# Volts_Sample.net
KiCad netlist of a schematic drawn in Altium Designer
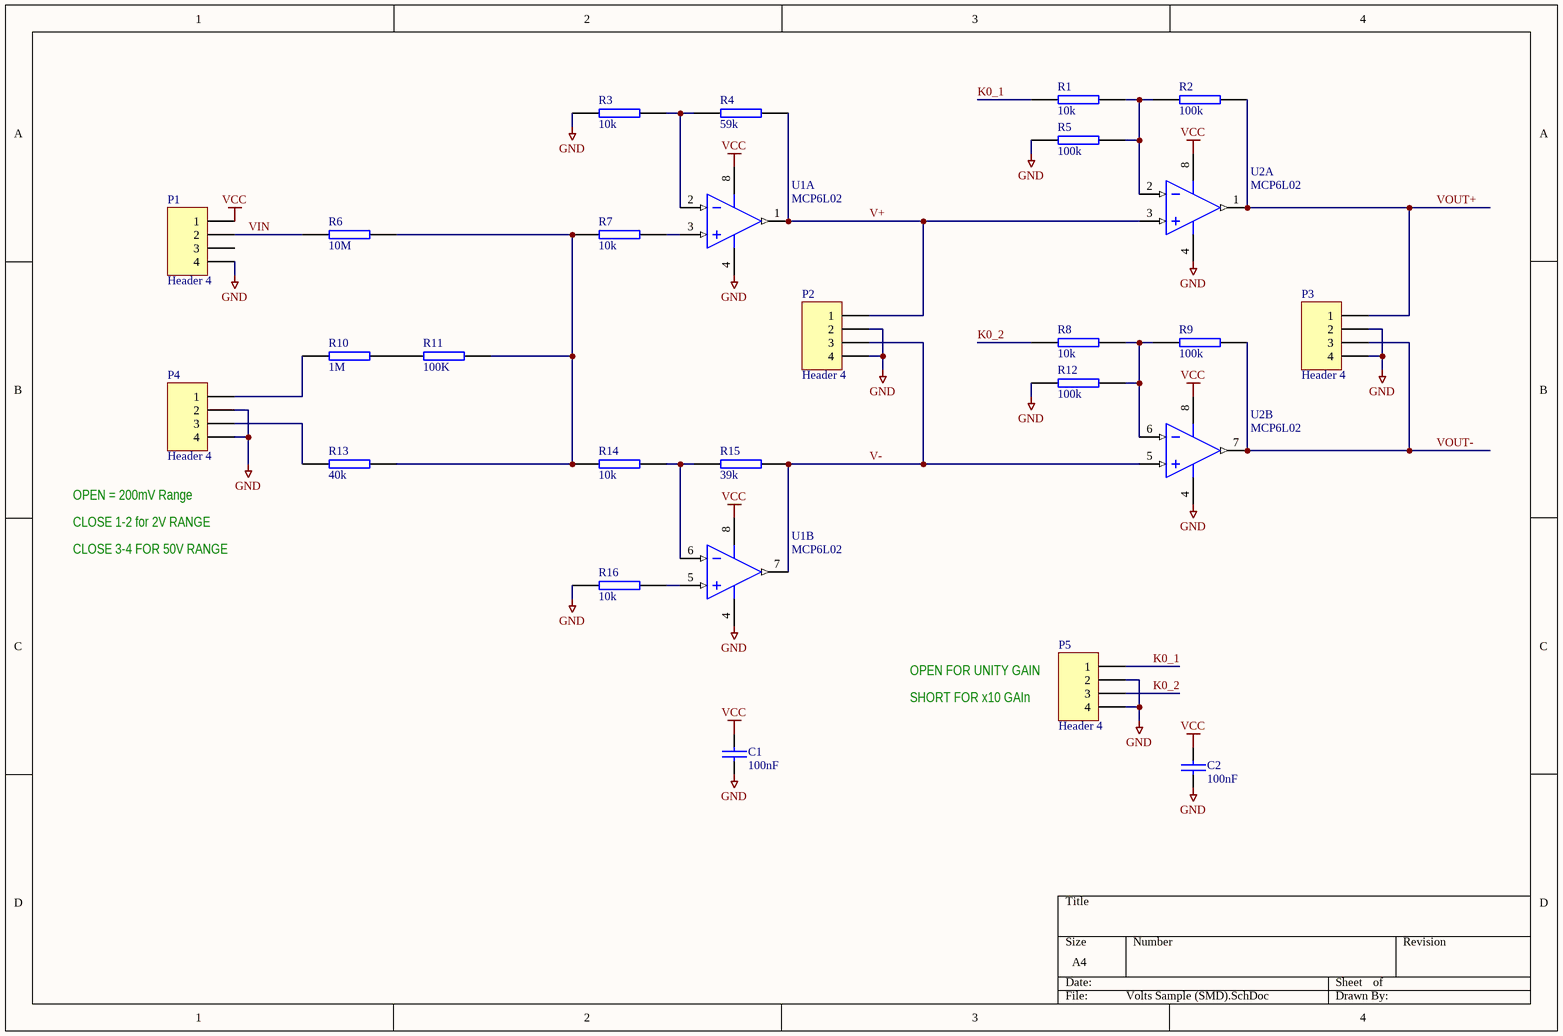
[diagram p0: Volts Sample (SMD).SchDoc]

(export (version "E")
  (design (tool "Eeschema 10.0.6"))
  (components
    (comp (ref "C1")
      (value "100nF")
      (footprint "CAP (3D) - 0603")
      (description "CAPACITOR SMD 0603")
      (fields
        (field (name "MOUSER PART NO.") "81-GRM155R61C104KA8D")
        (field (name "FARNELL PART NO.") "1414610")
      )
      (libsource (lib "Mi-Call Schematic") (part "CAP"))
    )
    (comp (ref "C2")
      (value "100nF")
      (footprint "CAP (3D) - 0603")
      (description "CAPACITOR SMD 0603")
      (fields
        (field (name "MOUSER PART NO.") "81-GRM155R61C104KA8D")
        (field (name "FARNELL PART NO.") "1414610")
      )
      (libsource (lib "Mi-Call Schematic") (part "CAP"))
    )
    (comp (ref "P1")
      (value "Header 4")
      (footprint "HDR1X4")
      (description "Header, 4-Pin")
      (fields (field (name "PUBLISHER") "Altium Limited"))
      (libsource (lib "Miscellaneous Connectors") (part "Header 4"))
    )
    (comp (ref "P2")
      (value "Header 4")
      (footprint "HDR1X4")
      (description "Header, 4-Pin")
      (fields (field (name "PUBLISHER") "Altium Limited"))
      (libsource (lib "Miscellaneous Connectors") (part "Header 4"))
    )
    (comp (ref "P3")
      (value "Header 4")
      (footprint "HDR1X4")
      (description "Header, 4-Pin")
      (fields (field (name "PUBLISHER") "Altium Limited"))
      (libsource (lib "Miscellaneous Connectors") (part "Header 4"))
    )
    (comp (ref "P4")
      (value "Header 4")
      (footprint "HDR1X4")
      (description "Header, 4-Pin")
      (fields (field (name "PUBLISHER") "Altium Limited"))
      (libsource (lib "Miscellaneous Connectors") (part "Header 4"))
    )
    (comp (ref "P5")
      (value "Header 4")
      (footprint "HDR1X4")
      (description "Header, 4-Pin")
      (fields (field (name "PUBLISHER") "Altium Limited"))
      (libsource (lib "Miscellaneous Connectors") (part "Header 4"))
    )
    (comp (ref "R1")
      (value "10k")
      (footprint "RES (3D) - 0603")
      (description "RESISTOR SMD 0603 10k")
      (fields (field (name "MOUSER PART NO.") "652-CR0603FX-1002ELF") (field (name "MANUFACTURER") "Bourns"))
      (libsource (lib "NASCO Resistors") (part "RES SMD 0603 10k"))
    )
    (comp (ref "R2")
      (value "100k")
      (footprint "RES (3D) - 0603")
      (description "RESISTOR SMD 0603 39k")
      (fields (field (name "MANUFACTURER") "Bourns"))
      (libsource (lib "NASCO Resistors") (part "RES SMD 0603 39k"))
    )
    (comp (ref "R3")
      (value "10k")
      (footprint "RES (3D) - 0603")
      (description "RESISTOR SMD 0603 10k")
      (fields (field (name "MOUSER PART NO.") "652-CR0603FX-1002ELF") (field (name "MANUFACTURER") "Bourns"))
      (libsource (lib "NASCO Resistors") (part "RES SMD 0603 10k"))
    )
    (comp (ref "R4")
      (value "59k")
      (footprint "RES (3D) - 0603")
      (description "RESISTOR SMD 0603 39k")
      (fields (field (name "MANUFACTURER") "Bourns"))
      (libsource (lib "NASCO Resistors") (part "RES SMD 0603 39k"))
    )
    (comp (ref "R5")
      (value "100k")
      (footprint "RES (3D) - 0603")
      (description "RESISTOR SMD 0603 39k")
      (fields (field (name "MANUFACTURER") "Bourns"))
      (libsource (lib "NASCO Resistors") (part "RES SMD 0603 39k"))
    )
    (comp (ref "R6")
      (value "10M")
      (footprint "RES (3D) - 0603")
      (description "RESISTOR SMD 0603 39k")
      (fields (field (name "MANUFACTURER") "Bourns"))
      (libsource (lib "NASCO Resistors") (part "RES SMD 0603 39k"))
    )
    (comp (ref "R7")
      (value "10k")
      (footprint "RES (3D) - 0603")
      (description "RESISTOR SMD 0603 10k")
      (fields (field (name "MOUSER PART NO.") "652-CR0603FX-1002ELF") (field (name "MANUFACTURER") "Bourns"))
      (libsource (lib "NASCO Resistors") (part "RES SMD 0603 10k"))
    )
    (comp (ref "R8")
      (value "10k")
      (footprint "RES (3D) - 0603")
      (description "RESISTOR SMD 0603 10k")
      (fields (field (name "MOUSER PART NO.") "652-CR0603FX-1002ELF") (field (name "MANUFACTURER") "Bourns"))
      (libsource (lib "NASCO Resistors") (part "RES SMD 0603 10k"))
    )
    (comp (ref "R9")
      (value "100k")
      (footprint "RES (3D) - 0603")
      (description "RESISTOR SMD 0603 39k")
      (fields (field (name "MANUFACTURER") "Bourns"))
      (libsource (lib "NASCO Resistors") (part "RES SMD 0603 39k"))
    )
    (comp (ref "R10")
      (value "1M")
      (footprint "RES (3D) - 0603")
      (description "RESISTOR SMD 0603 39k")
      (fields (field (name "MANUFACTURER") "Bourns"))
      (libsource (lib "NASCO Resistors") (part "RES SMD 0603 39k"))
    )
    (comp (ref "R11")
      (value "100K")
      (footprint "RES (3D) - 0603")
      (description "RESISTOR SMD 0603 39k")
      (fields (field (name "MANUFACTURER") "Bourns"))
      (libsource (lib "NASCO Resistors") (part "RES SMD 0603 39k"))
    )
    (comp (ref "R12")
      (value "100k")
      (footprint "RES (3D) - 0603")
      (description "RESISTOR SMD 0603 39k")
      (fields (field (name "MANUFACTURER") "Bourns"))
      (libsource (lib "NASCO Resistors") (part "RES SMD 0603 39k"))
    )
    (comp (ref "R13")
      (value "40k")
      (footprint "RES (3D) - 0603")
      (description "RESISTOR SMD 0603 39k")
      (fields (field (name "MANUFACTURER") "Bourns"))
      (libsource (lib "NASCO Resistors") (part "RES SMD 0603 39k"))
    )
    (comp (ref "R14")
      (value "10k")
      (footprint "RES (3D) - 0603")
      (description "RESISTOR SMD 0603 10k")
      (fields (field (name "MOUSER PART NO.") "652-CR0603FX-1002ELF") (field (name "MANUFACTURER") "Bourns"))
      (libsource (lib "NASCO Resistors") (part "RES SMD 0603 10k"))
    )
    (comp (ref "R15")
      (value "39k")
      (footprint "RES (3D) - 0603")
      (description "RESISTOR SMD 0603 39k")
      (fields (field (name "MOUSER PART NO.") "652-CR0603FX-3902ELF") (field (name "MANUFACTURER") "Bourns"))
      (libsource (lib "NASCO Resistors") (part "RES SMD 0603 39k"))
    )
    (comp (ref "R16")
      (value "10k")
      (footprint "RES (3D) - 0603")
      (description "RESISTOR SMD 0603 10k")
      (fields (field (name "MOUSER PART NO.") "652-CR0603FX-1002ELF") (field (name "MANUFACTURER") "Bourns"))
      (libsource (lib "NASCO Resistors") (part "RES SMD 0603 10k"))
    )
    (comp (ref "U1") (value "MCP6L02") (footprint "SO-8") (libsource (lib "MCPL02") (part "MCP6L02")))
    (comp (ref "U2") (value "MCP6L02") (footprint "SO-8") (libsource (lib "MCPL02") (part "MCP6L02")))
  )
  (nets
    (net (code "1") (name "/K0_1") (class "Default")
      (node (ref "P5") (pin "1") (pinfunction "1_1") (pintype "passive"))
      (node (ref "R1") (pin "1") (pinfunction "1_1") (pintype "passive"))
    )
    (net (code "2") (name "/K0_2") (class "Default")
      (node (ref "P5") (pin "3") (pinfunction "3_3") (pintype "passive"))
      (node (ref "R8") (pin "1") (pinfunction "1_1") (pintype "passive"))
    )
    (net (code "3") (name "/V+") (class "Default")
      (node (ref "P2") (pin "1") (pinfunction "1_1") (pintype "passive"))
      (node (ref "R4") (pin "2") (pinfunction "2_2") (pintype "passive"))
      (node (ref "U1") (pin "1") (pinfunction "OUTA_1") (pintype "output"))
      (node (ref "U2") (pin "3") (pinfunction "INA+_3") (pintype "input"))
    )
    (net (code "4") (name "/V-") (class "Default")
      (node (ref "P2") (pin "3") (pinfunction "3_3") (pintype "passive"))
      (node (ref "R15") (pin "2") (pinfunction "2_2") (pintype "passive"))
      (node (ref "U1") (pin "7") (pinfunction "OUTB_7") (pintype "output"))
      (node (ref "U2") (pin "5") (pinfunction "INB+_5") (pintype "input"))
    )
    (net (code "5") (name "/VIN") (class "Default")
      (node (ref "P1") (pin "2") (pinfunction "2_2") (pintype "passive"))
      (node (ref "R6") (pin "1") (pinfunction "1_1") (pintype "passive"))
    )
    (net (code "6") (name "/VOUT+") (class "Default")
      (node (ref "P3") (pin "1") (pinfunction "1_1") (pintype "passive"))
      (node (ref "R2") (pin "2") (pinfunction "2_2") (pintype "passive"))
      (node (ref "U2") (pin "1") (pinfunction "OUTA_1") (pintype "output"))
    )
    (net (code "7") (name "/VOUT-") (class "Default")
      (node (ref "P3") (pin "3") (pinfunction "3_3") (pintype "passive"))
      (node (ref "R9") (pin "2") (pinfunction "2_2") (pintype "passive"))
      (node (ref "U2") (pin "7") (pinfunction "OUTB_7") (pintype "output"))
    )
    (net (code "8") (name "GND") (class "Default")
      (node (ref "C1") (pin "2") (pinfunction "2_2") (pintype "passive"))
      (node (ref "C2") (pin "2") (pinfunction "2_2") (pintype "passive"))
      (node (ref "P1") (pin "4") (pinfunction "4_4") (pintype "passive"))
      (node (ref "P2") (pin "2") (pinfunction "2_2") (pintype "passive"))
      (node (ref "P2") (pin "4") (pinfunction "4_4") (pintype "passive"))
      (node (ref "P3") (pin "2") (pinfunction "2_2") (pintype "passive"))
      (node (ref "P3") (pin "4") (pinfunction "4_4") (pintype "passive"))
      (node (ref "P4") (pin "2") (pinfunction "2_2") (pintype "passive"))
      (node (ref "P4") (pin "4") (pinfunction "4_4") (pintype "passive"))
      (node (ref "P5") (pin "2") (pinfunction "2_2") (pintype "passive"))
      (node (ref "P5") (pin "4") (pinfunction "4_4") (pintype "passive"))
      (node (ref "R12") (pin "1") (pinfunction "1_1") (pintype "passive"))
      (node (ref "R16") (pin "1") (pinfunction "1_1") (pintype "passive"))
      (node (ref "R3") (pin "1") (pinfunction "1_1") (pintype "passive"))
      (node (ref "R5") (pin "1") (pinfunction "1_1") (pintype "passive"))
      (node (ref "U1") (pin "4") (pinfunction "GND_4") (pintype "power_in"))
      (node (ref "U2") (pin "4") (pinfunction "GND_4") (pintype "power_in"))
    )
    (net (code "9") (name "Net-(P4-Pad1)") (class "Default")
      (node (ref "P4") (pin "1") (pinfunction "1_1") (pintype "passive"))
      (node (ref "R10") (pin "1") (pinfunction "1_1") (pintype "passive"))
    )
    (net (code "10") (name "Net-(P4-Pad3)") (class "Default")
      (node (ref "P4") (pin "3") (pinfunction "3_3") (pintype "passive"))
      (node (ref "R13") (pin "1") (pinfunction "1_1") (pintype "passive"))
    )
    (net (code "11") (name "Net-(R10-Pad2)") (class "Default")
      (node (ref "R10") (pin "2") (pinfunction "2_2") (pintype "passive"))
      (node (ref "R11") (pin "1") (pinfunction "1_1") (pintype "passive"))
    )
    (net (code "12") (name "Net-(R11-Pad2)") (class "Default")
      (node (ref "R11") (pin "2") (pinfunction "2_2") (pintype "passive"))
      (node (ref "R13") (pin "2") (pinfunction "2_2") (pintype "passive"))
      (node (ref "R14") (pin "1") (pinfunction "1_1") (pintype "passive"))
      (node (ref "R6") (pin "2") (pinfunction "2_2") (pintype "passive"))
      (node (ref "R7") (pin "1") (pinfunction "1_1") (pintype "passive"))
    )
    (net (code "13") (name "Net-(U1A-INA+)") (class "Default")
      (node (ref "R7") (pin "2") (pinfunction "2_2") (pintype "passive"))
      (node (ref "U1") (pin "3") (pinfunction "INA+_3") (pintype "input"))
    )
    (net (code "14") (name "Net-(U1A-INA-)") (class "Default")
      (node (ref "R3") (pin "2") (pinfunction "2_2") (pintype "passive"))
      (node (ref "R4") (pin "1") (pinfunction "1_1") (pintype "passive"))
      (node (ref "U1") (pin "2") (pinfunction "INA-_2") (pintype "input"))
    )
    (net (code "15") (name "Net-(U1B-INB+)") (class "Default")
      (node (ref "R16") (pin "2") (pinfunction "2_2") (pintype "passive"))
      (node (ref "U1") (pin "5") (pinfunction "INB+_5") (pintype "input"))
    )
    (net (code "16") (name "Net-(U1B-INB-)") (class "Default")
      (node (ref "R14") (pin "2") (pinfunction "2_2") (pintype "passive"))
      (node (ref "R15") (pin "1") (pinfunction "1_1") (pintype "passive"))
      (node (ref "U1") (pin "6") (pinfunction "INB-_6") (pintype "input"))
    )
    (net (code "17") (name "Net-(U2A-INA-)") (class "Default")
      (node (ref "R1") (pin "2") (pinfunction "2_2") (pintype "passive"))
      (node (ref "R2") (pin "1") (pinfunction "1_1") (pintype "passive"))
      (node (ref "R5") (pin "2") (pinfunction "2_2") (pintype "passive"))
      (node (ref "U2") (pin "2") (pinfunction "INA-_2") (pintype "input"))
    )
    (net (code "18") (name "Net-(U2B-INB-)") (class "Default")
      (node (ref "R12") (pin "2") (pinfunction "2_2") (pintype "passive"))
      (node (ref "R8") (pin "2") (pinfunction "2_2") (pintype "passive"))
      (node (ref "R9") (pin "1") (pinfunction "1_1") (pintype "passive"))
      (node (ref "U2") (pin "6") (pinfunction "INB-_6") (pintype "input"))
    )
    (net (code "19") (name "VCC") (class "Default")
      (node (ref "C1") (pin "1") (pinfunction "1_1") (pintype "passive"))
      (node (ref "C2") (pin "1") (pinfunction "1_1") (pintype "passive"))
      (node (ref "P1") (pin "1") (pinfunction "1_1") (pintype "passive"))
      (node (ref "U1") (pin "8") (pinfunction "V+_8") (pintype "power_in"))
      (node (ref "U2") (pin "8") (pinfunction "V+_8") (pintype "power_in"))
    )
    (net (code "20") (name "unconnected-(P1-Pad3)") (class "Default")
      (node (ref "P1") (pin "3") (pinfunction "3_3") (pintype "passive"))
    )
  )
)
